# memory.net
KiCad netlist of a schematic drawn in Altium Designer
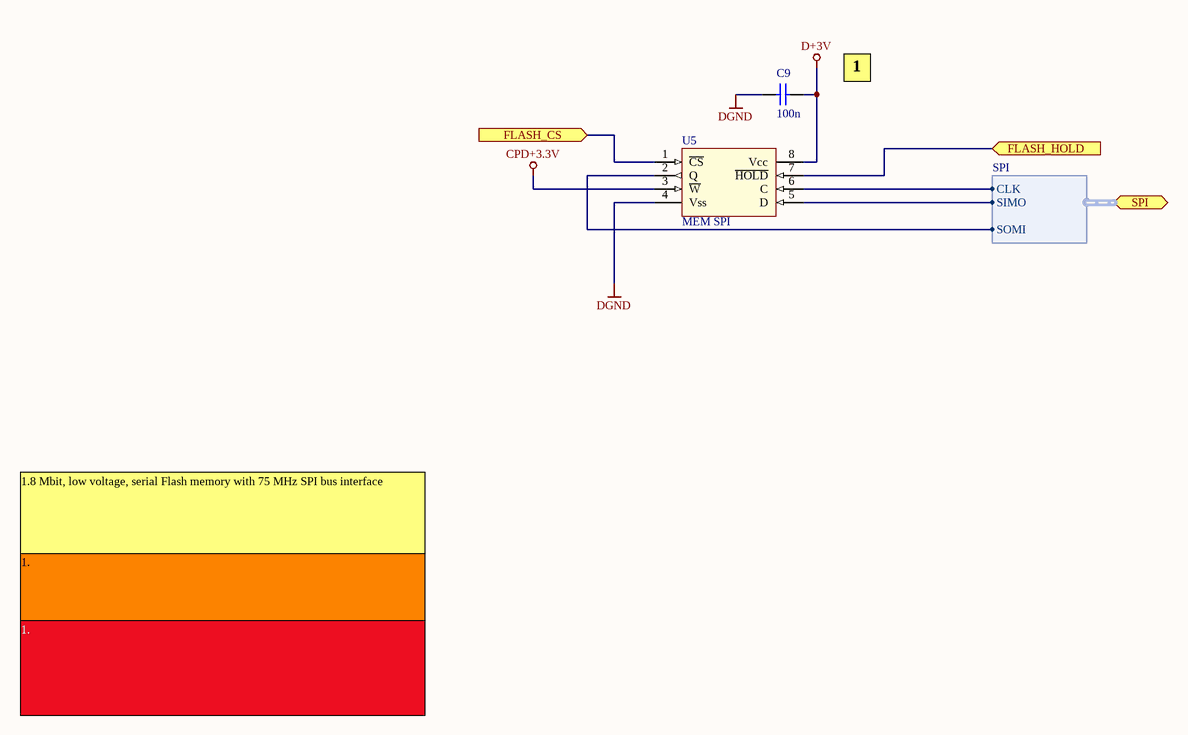
[diagram p0: memory.SchDoc]

(export (version "E")
  (design (tool "Eeschema 10.0.6"))
  (components
    (comp (ref "C9")
      (value "100n")
      (footprint "CC-0402-AL")
      (description "Capacitor (Semiconductor SIM Model)")
      (fields (field (name "Comment") "Cap Semi"))
      (libsource (lib "Z1_Project") (part "Cap Semi"))
    )
    (comp (ref "U5")
      (value "MEM SPI")
      (footprint "VFQFPN8")
      (description "8 Mbit, low voltage, serial Flash memory  with 75 MHz SPI bus interface")
      (libsource (lib "Z1_Project") (part "M25P80"))
    )
  )
  (nets
    (net (code "2") (name "/CLK") (class "Default")
      (node (ref "U5") (pin "6") (pinfunction "C_6") (pintype "input"))
    )
    (net (code "3") (name "/FLASH_CS") (class "Default")
      (node (ref "U5") (pin "1") (pinfunction "~{CS}_1") (pintype "input"))
    )
    (net (code "4") (name "/FLASH_HOLD") (class "Default")
      (node (ref "U5") (pin "7") (pinfunction "~{HOLD}_7") (pintype "input"))
    )
    (net (code "5") (name "/SIMO") (class "Default")
      (node (ref "U5") (pin "5") (pinfunction "D_5") (pintype "input"))
    )
    (net (code "6") (name "/SOMI") (class "Default")
      (node (ref "U5") (pin "2") (pinfunction "Q_2") (pintype "output"))
    )
    (net (code "8") (name "CPD+3.3V") (class "Default")
      (node (ref "U5") (pin "3") (pinfunction "~{W}_3") (pintype "input"))
    )
    (net (code "9") (name "D+3V") (class "Default")
      (node (ref "C9") (pin "2") (pinfunction "2_2") (pintype "passive"))
      (node (ref "U5") (pin "8") (pinfunction "Vcc_8") (pintype "power_in"))
    )
    (net (code "10") (name "DGND") (class "Default")
      (node (ref "C9") (pin "1") (pinfunction "1_1") (pintype "passive"))
      (node (ref "U5") (pin "4") (pinfunction "Vss_4") (pintype "power_in"))
    )
  )
)
